# pwr_supply_board.net
KiCad netlist of a schematic drawn in EAGLE
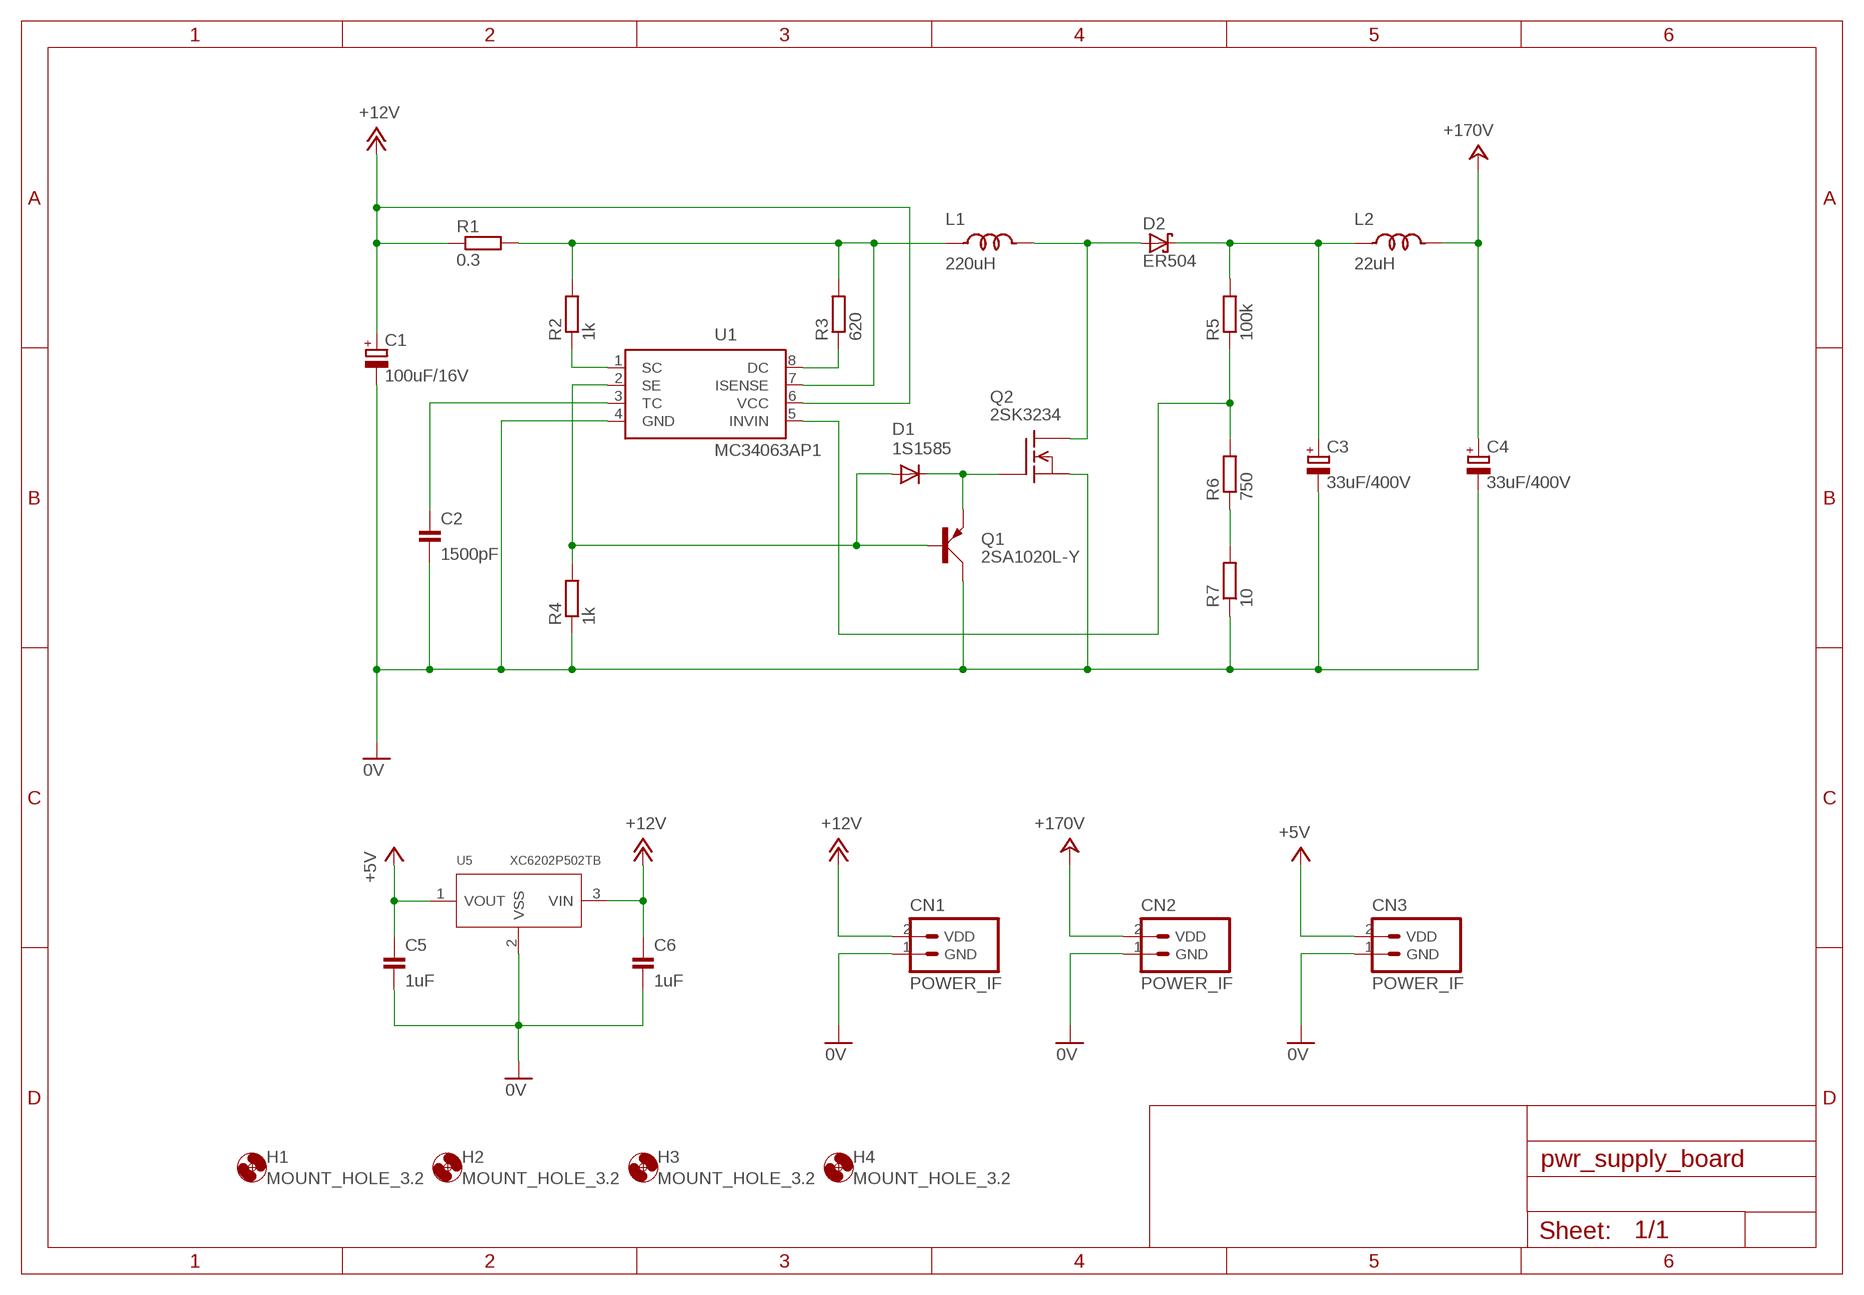
[diagram p0: schematic, sheet 1]

(export (version "E")
  (design (tool "Eeschema 10.0.6"))
  (components
    (comp (ref "C1")
      (value "100uF/16V")
      (footprint "eagle-import:ELECAP_100MIL")
      (libsource (lib "eagle-import") (part "ELECAP_100MIL"))
    )
    (comp (ref "C2")
      (value "1500pF")
      (footprint "eagle-import:CAP_100MIL")
      (libsource (lib "eagle-import") (part "CAP_100MIL"))
    )
    (comp (ref "C3")
      (value "33uF/400V")
      (footprint "eagle-import:ELECAP_300MIL")
      (libsource (lib "eagle-import") (part "ELECAP_300MIL"))
    )
    (comp (ref "C4")
      (value "33uF/400V")
      (footprint "eagle-import:ELECAP_300MIL")
      (libsource (lib "eagle-import") (part "ELECAP_300MIL"))
    )
    (comp (ref "C5")
      (value "1uF")
      (footprint "eagle-import:CAP_100MIL")
      (libsource (lib "eagle-import") (part "CAP_100MIL"))
    )
    (comp (ref "C6")
      (value "1uF")
      (footprint "eagle-import:CAP_100MIL")
      (libsource (lib "eagle-import") (part "CAP_100MIL"))
    )
    (comp (ref "CN1")
      (value "POWER_IF")
      (footprint "eagle-import:HEADER_2PIN_POWER_IF")
      (libsource (lib "eagle-import") (part "POWER_IF"))
    )
    (comp (ref "CN2")
      (value "POWER_IF")
      (footprint "eagle-import:HEADER_2PIN_POWER_IF")
      (libsource (lib "eagle-import") (part "POWER_IF"))
    )
    (comp (ref "CN3")
      (value "POWER_IF")
      (footprint "eagle-import:HEADER_2PIN_POWER_IF")
      (libsource (lib "eagle-import") (part "POWER_IF"))
    )
    (comp (ref "D1")
      (value "1S1585")
      (footprint "eagle-import:DIODE-200MIL")
      (libsource (lib "eagle-import") (part "1S1585"))
    )
    (comp (ref "D2")
      (value "ER504")
      (footprint "eagle-import:DIODE-500MIL")
      (libsource (lib "eagle-import") (part "ER504"))
    )
    (comp (ref "H1")
      (value "MOUNT_HOLE_3.2")
      (footprint "eagle-import:3,2")
      (libsource (lib "eagle-import") (part "MOUNT_HOLE_3.2"))
    )
    (comp (ref "H2")
      (value "MOUNT_HOLE_3.2")
      (footprint "eagle-import:3,2")
      (libsource (lib "eagle-import") (part "MOUNT_HOLE_3.2"))
    )
    (comp (ref "H3")
      (value "MOUNT_HOLE_3.2")
      (footprint "eagle-import:3,2")
      (libsource (lib "eagle-import") (part "MOUNT_HOLE_3.2"))
    )
    (comp (ref "H4")
      (value "MOUNT_HOLE_3.2")
      (footprint "eagle-import:3,2")
      (libsource (lib "eagle-import") (part "MOUNT_HOLE_3.2"))
    )
    (comp (ref "L1")
      (value "220uH")
      (footprint "eagle-import:TOROID_COIL-300MIL")
      (libsource (lib "eagle-import") (part "TC5026-220UH-050"))
    )
    (comp (ref "L2")
      (value "22uH")
      (footprint "eagle-import:TOROID_COIL-300MIL")
      (libsource (lib "eagle-import") (part "TC5026-22UH-060"))
    )
    (comp (ref "Q1")
      (value "2SA1020L-Y")
      (footprint "eagle-import:TO-92NL")
      (libsource (lib "eagle-import") (part "2SA1020L-Y"))
    )
    (comp (ref "Q2")
      (value "2SK3234")
      (footprint "eagle-import:TO-220")
      (libsource (lib "eagle-import") (part "2SK3234"))
    )
    (comp (ref "R1")
      (value "0.3")
      (footprint "eagle-import:RESISTOR_0411_600MIL")
      (libsource (lib "eagle-import") (part "RESISTOR_600MIL"))
    )
    (comp (ref "R2")
      (value "1k")
      (footprint "eagle-import:RESISTOR_0411_600MIL")
      (libsource (lib "eagle-import") (part "RESISTOR_600MIL"))
    )
    (comp (ref "R3")
      (value "620")
      (footprint "eagle-import:RESISTOR_0411_600MIL")
      (libsource (lib "eagle-import") (part "RESISTOR_600MIL"))
    )
    (comp (ref "R4")
      (value "1k")
      (footprint "eagle-import:RESISTOR_0411_600MIL")
      (libsource (lib "eagle-import") (part "RESISTOR_600MIL"))
    )
    (comp (ref "R5")
      (value "100k")
      (footprint "eagle-import:RESISTOR_0411_600MIL")
      (libsource (lib "eagle-import") (part "RESISTOR_600MIL"))
    )
    (comp (ref "R6")
      (value "750")
      (footprint "eagle-import:RESISTOR_0411_600MIL")
      (libsource (lib "eagle-import") (part "RESISTOR_600MIL"))
    )
    (comp (ref "R7")
      (value "10")
      (footprint "eagle-import:RESISTOR_0411_600MIL")
      (libsource (lib "eagle-import") (part "RESISTOR_600MIL"))
    )
    (comp (ref "U1")
      (value "MC34063AP1")
      (footprint "eagle-import:DIL08")
      (libsource (lib "eagle-import") (part "MC34063AP1"))
    )
    (comp (ref "U5")
      (value "XC6202P502TB")
      (footprint "eagle-import:TO92-LINE")
      (libsource (lib "eagle-import") (part "XC6202P502TB"))
    )
  )
  (nets
    (net (code "1") (name "+5V") (class "Default")
      (node (ref "C5") (pin "1") (pinfunction "1_1") (pintype "passive"))
      (node (ref "CN3") (pin "2") (pinfunction "VDD_2") (pintype "passive"))
      (node (ref "U5") (pin "1") (pinfunction "VOUT_1") (pintype "passive"))
    )
    (net (code "2") (name "+12V") (class "Default")
      (node (ref "C1") (pin "+") (pinfunction "+_+") (pintype "passive"))
      (node (ref "C6") (pin "1") (pinfunction "1_1") (pintype "passive"))
      (node (ref "CN1") (pin "2") (pinfunction "VDD_2") (pintype "passive"))
      (node (ref "R1") (pin "1") (pinfunction "1_1") (pintype "passive"))
      (node (ref "U1") (pin "6") (pinfunction "VCC_6") (pintype "passive"))
      (node (ref "U5") (pin "3") (pinfunction "VIN_3") (pintype "passive"))
    )
    (net (code "3") (name "+170V") (class "Default")
      (node (ref "C4") (pin "+") (pinfunction "+_+") (pintype "passive"))
      (node (ref "CN2") (pin "2") (pinfunction "VDD_2") (pintype "passive"))
      (node (ref "L2") (pin "2") (pinfunction "2_2") (pintype "passive"))
    )
    (net (code "4") (name "0V") (class "Default")
      (node (ref "C1") (pin "-") (pinfunction "-_-") (pintype "passive"))
      (node (ref "C2") (pin "2") (pinfunction "2_2") (pintype "passive"))
      (node (ref "C3") (pin "-") (pinfunction "-_-") (pintype "passive"))
      (node (ref "C4") (pin "-") (pinfunction "-_-") (pintype "passive"))
      (node (ref "C5") (pin "2") (pinfunction "2_2") (pintype "passive"))
      (node (ref "C6") (pin "2") (pinfunction "2_2") (pintype "passive"))
      (node (ref "CN1") (pin "1") (pinfunction "GND_1") (pintype "passive"))
      (node (ref "CN2") (pin "1") (pinfunction "GND_1") (pintype "passive"))
      (node (ref "CN3") (pin "1") (pinfunction "GND_1") (pintype "passive"))
      (node (ref "Q1") (pin "2") (pinfunction "C_2") (pintype "passive"))
      (node (ref "Q2") (pin "3") (pinfunction "S_3") (pintype "passive"))
      (node (ref "R4") (pin "1") (pinfunction "1_1") (pintype "passive"))
      (node (ref "R7") (pin "1") (pinfunction "1_1") (pintype "passive"))
      (node (ref "U1") (pin "4") (pinfunction "GND_4") (pintype "passive"))
      (node (ref "U5") (pin "2") (pinfunction "VSS_2") (pintype "passive"))
    )
    (net (code "5") (name "Net-(C3-Pad+)") (class "Default")
      (node (ref "C3") (pin "+") (pinfunction "+_+") (pintype "passive"))
      (node (ref "D2") (pin "C") (pinfunction "C_C") (pintype "passive"))
      (node (ref "L2") (pin "1") (pinfunction "1_1") (pintype "passive"))
      (node (ref "R5") (pin "2") (pinfunction "2_2") (pintype "passive"))
    )
    (net (code "6") (name "Net-(Q1-B)") (class "Default")
      (node (ref "D1") (pin "A") (pinfunction "A_A") (pintype "passive"))
      (node (ref "Q1") (pin "3") (pinfunction "B_3") (pintype "passive"))
      (node (ref "R4") (pin "2") (pinfunction "2_2") (pintype "passive"))
      (node (ref "U1") (pin "2") (pinfunction "SE_2") (pintype "passive"))
    )
    (net (code "7") (name "Net-(Q1-E)") (class "Default")
      (node (ref "D1") (pin "C") (pinfunction "C_C") (pintype "passive"))
      (node (ref "Q1") (pin "1") (pinfunction "E_1") (pintype "passive"))
      (node (ref "Q2") (pin "1") (pinfunction "G_1") (pintype "passive"))
    )
    (net (code "8") (name "Net-(Q2-D)") (class "Default")
      (node (ref "D2") (pin "A") (pinfunction "A_A") (pintype "passive"))
      (node (ref "L1") (pin "2") (pinfunction "2_2") (pintype "passive"))
      (node (ref "Q2") (pin "2") (pinfunction "D_2") (pintype "passive"))
    )
    (net (code "9") (name "Net-(R6-Pad1)") (class "Default")
      (node (ref "R6") (pin "1") (pinfunction "1_1") (pintype "passive"))
      (node (ref "R7") (pin "2") (pinfunction "2_2") (pintype "passive"))
    )
    (net (code "10") (name "Net-(U1-DC)") (class "Default")
      (node (ref "R3") (pin "1") (pinfunction "1_1") (pintype "passive"))
      (node (ref "U1") (pin "8") (pinfunction "DC_8") (pintype "passive"))
    )
    (net (code "11") (name "Net-(U1-INVIN)") (class "Default")
      (node (ref "R5") (pin "1") (pinfunction "1_1") (pintype "passive"))
      (node (ref "R6") (pin "2") (pinfunction "2_2") (pintype "passive"))
      (node (ref "U1") (pin "5") (pinfunction "INVIN_5") (pintype "passive"))
    )
    (net (code "12") (name "Net-(U1-ISENSE)") (class "Default")
      (node (ref "L1") (pin "1") (pinfunction "1_1") (pintype "passive"))
      (node (ref "R1") (pin "2") (pinfunction "2_2") (pintype "passive"))
      (node (ref "R2") (pin "2") (pinfunction "2_2") (pintype "passive"))
      (node (ref "R3") (pin "2") (pinfunction "2_2") (pintype "passive"))
      (node (ref "U1") (pin "7") (pinfunction "ISENSE_7") (pintype "passive"))
    )
    (net (code "13") (name "Net-(U1-SC)") (class "Default")
      (node (ref "R2") (pin "1") (pinfunction "1_1") (pintype "passive"))
      (node (ref "U1") (pin "1") (pinfunction "SC_1") (pintype "passive"))
    )
    (net (code "14") (name "Net-(U1-TC)") (class "Default")
      (node (ref "C2") (pin "1") (pinfunction "1_1") (pintype "passive"))
      (node (ref "U1") (pin "3") (pinfunction "TC_3") (pintype "passive"))
    )
  )
)
